# Sheet2.net
KiCad netlist of a schematic drawn in Altium Designer
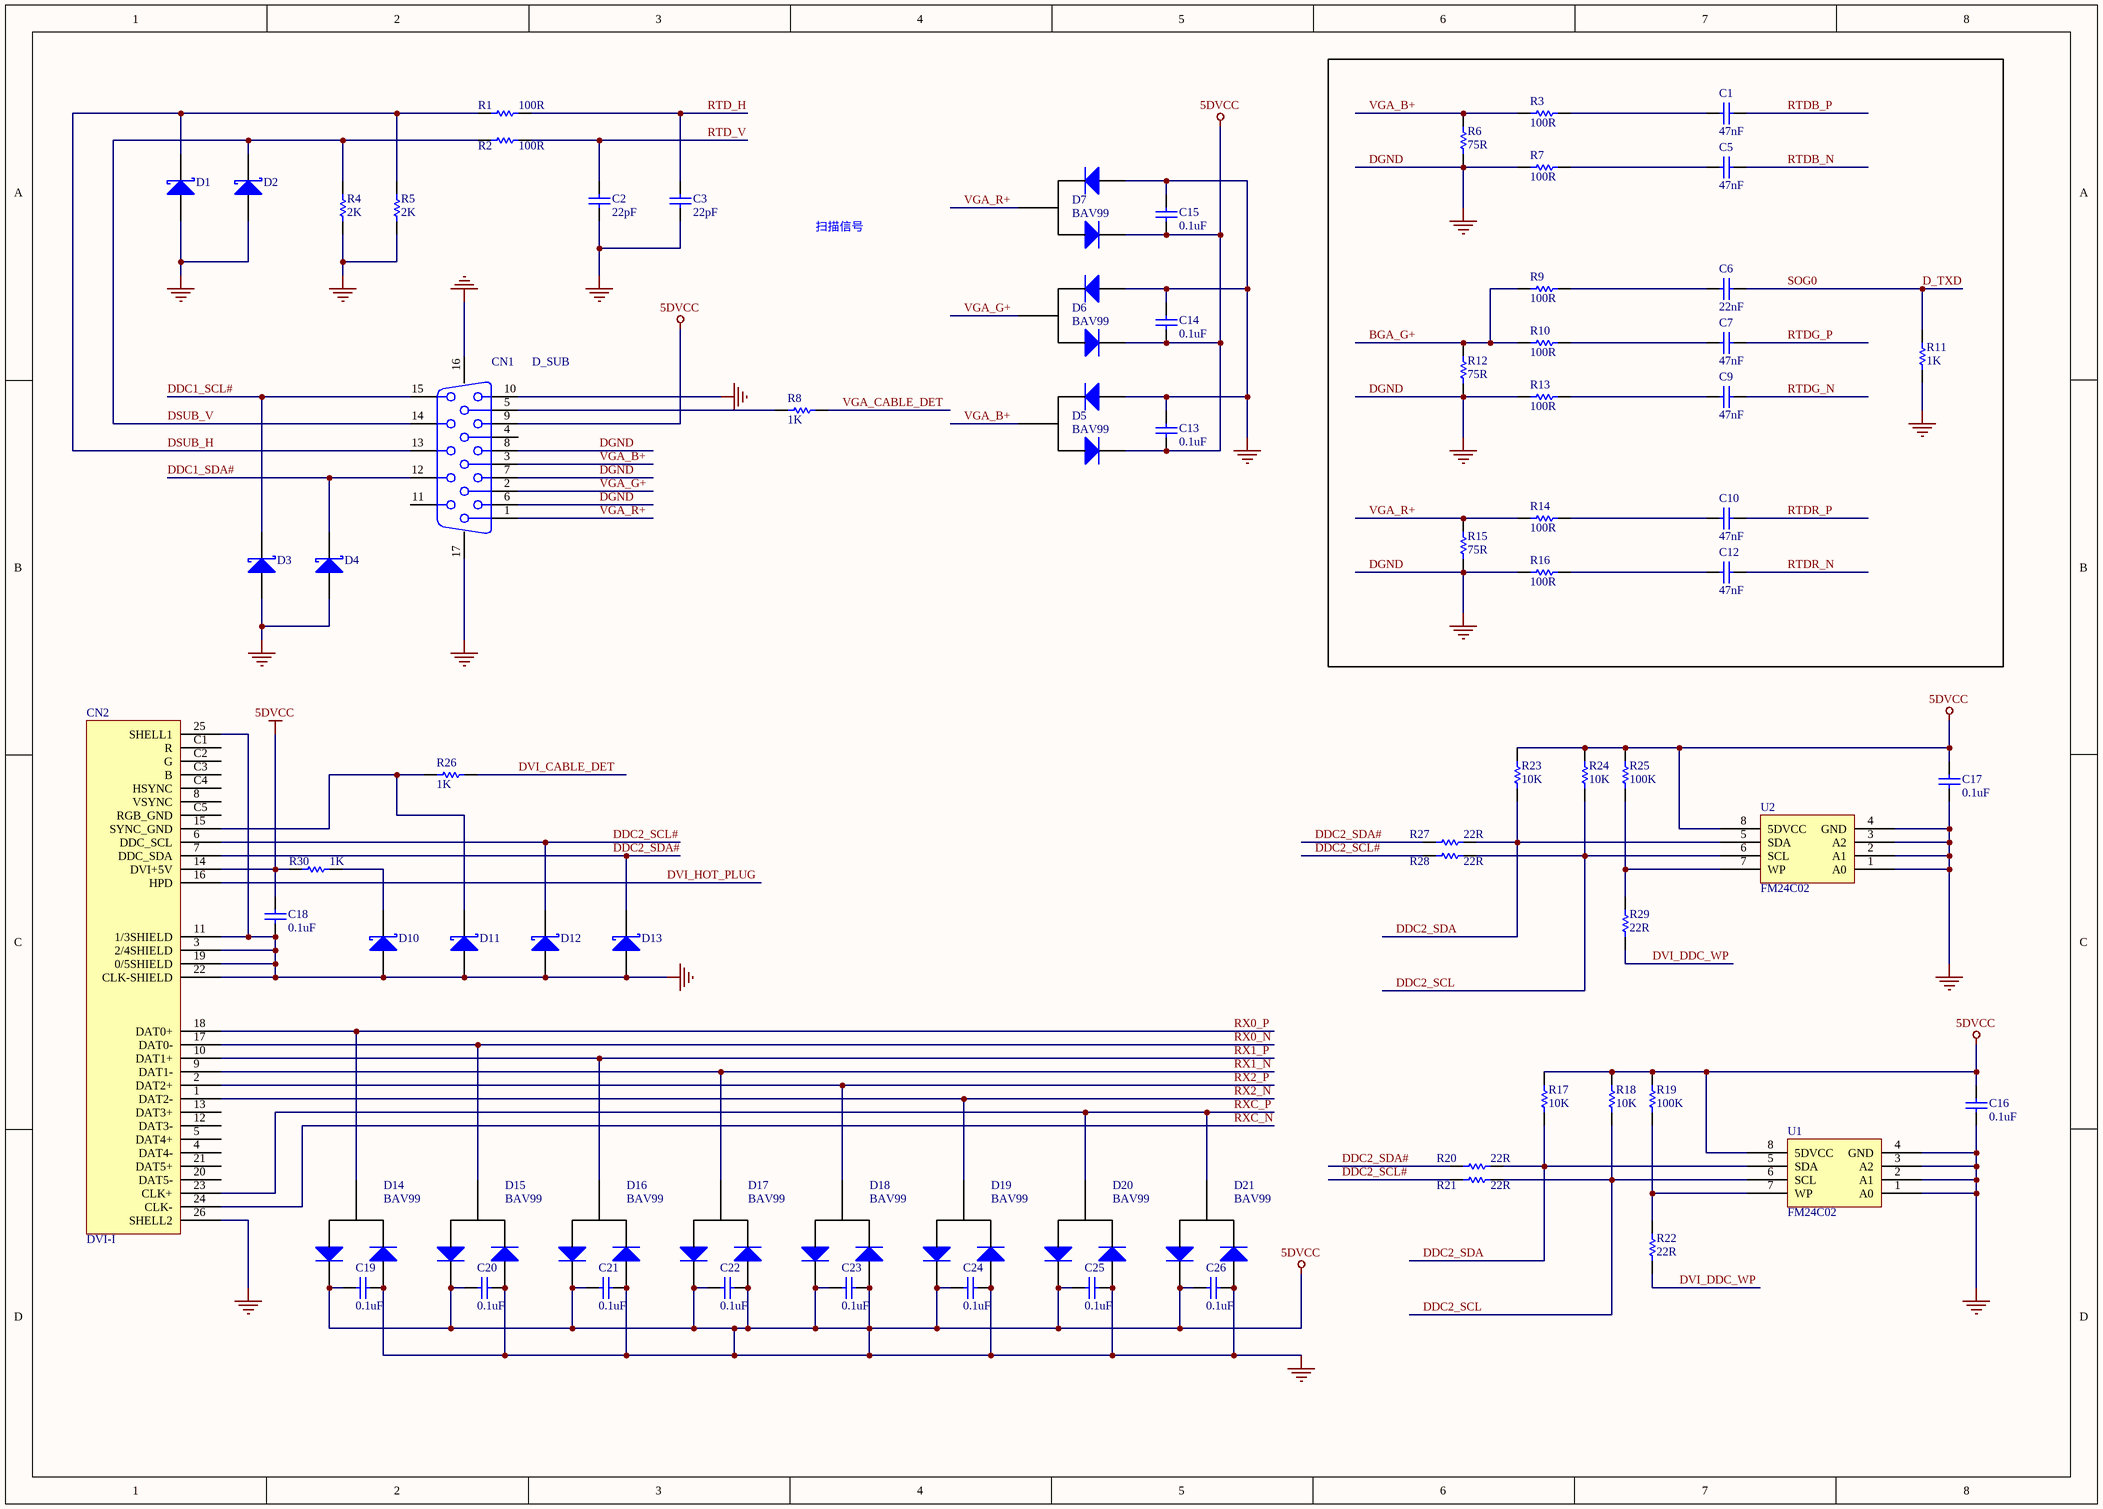
[diagram p0: Sheet2.SchDoc]

(export (version "E")
  (design (tool "Eeschema 10.0.6"))
  (components
    (comp (ref "C1")
      (value "47nF")
      (footprint "C-0402")
      (description "Capacitor")
      (fields (field (name "Comment") "Cap") (field (name "PUBLISHER") "Altium Limited"))
      (libsource (lib "Miscellaneous Devices") (part "Cap"))
    )
    (comp (ref "C2")
      (value "22pF")
      (footprint "C-0402")
      (description "Capacitor")
      (fields (field (name "Comment") "Cap") (field (name "PUBLISHER") "Altium Limited"))
      (libsource (lib "Miscellaneous Devices") (part "Cap"))
    )
    (comp (ref "C3")
      (value "22pF")
      (footprint "C-0402")
      (description "Capacitor")
      (fields (field (name "Comment") "Cap") (field (name "PUBLISHER") "Altium Limited"))
      (libsource (lib "Miscellaneous Devices") (part "Cap"))
    )
    (comp (ref "C5")
      (value "47nF")
      (footprint "C-0402")
      (description "Capacitor")
      (fields (field (name "Comment") "Cap") (field (name "PUBLISHER") "Altium Limited"))
      (libsource (lib "Miscellaneous Devices") (part "Cap"))
    )
    (comp (ref "C6")
      (value "22nF")
      (footprint "C-0402")
      (description "Capacitor")
      (fields (field (name "Comment") "Cap") (field (name "PUBLISHER") "Altium Limited"))
      (libsource (lib "Miscellaneous Devices") (part "Cap"))
    )
    (comp (ref "C7")
      (value "47nF")
      (footprint "C-0402")
      (description "Capacitor")
      (fields (field (name "Comment") "Cap") (field (name "PUBLISHER") "Altium Limited"))
      (libsource (lib "Miscellaneous Devices") (part "Cap"))
    )
    (comp (ref "C9")
      (value "47nF")
      (footprint "C-0402")
      (description "Capacitor")
      (fields (field (name "Comment") "Cap") (field (name "PUBLISHER") "Altium Limited"))
      (libsource (lib "Miscellaneous Devices") (part "Cap"))
    )
    (comp (ref "C10")
      (value "47nF")
      (footprint "C-0402")
      (description "Capacitor")
      (fields (field (name "Comment") "Cap") (field (name "PUBLISHER") "Altium Limited"))
      (libsource (lib "Miscellaneous Devices") (part "Cap"))
    )
    (comp (ref "C12")
      (value "47nF")
      (footprint "C-0402")
      (description "Capacitor")
      (fields (field (name "Comment") "Cap") (field (name "PUBLISHER") "Altium Limited"))
      (libsource (lib "Miscellaneous Devices") (part "Cap"))
    )
    (comp (ref "C13")
      (value "0.1uF")
      (footprint "C-0402")
      (description "Capacitor")
      (fields (field (name "Comment") "Cap") (field (name "PUBLISHER") "Altium Limited"))
      (libsource (lib "Miscellaneous Devices") (part "Cap"))
    )
    (comp (ref "C14")
      (value "0.1uF")
      (footprint "C-0402")
      (description "Capacitor")
      (fields (field (name "Comment") "Cap") (field (name "PUBLISHER") "Altium Limited"))
      (libsource (lib "Miscellaneous Devices") (part "Cap"))
    )
    (comp (ref "C15")
      (value "0.1uF")
      (footprint "C-0402")
      (description "Capacitor")
      (fields (field (name "Comment") "Cap") (field (name "PUBLISHER") "Altium Limited"))
      (libsource (lib "Miscellaneous Devices") (part "Cap"))
    )
    (comp (ref "C16")
      (value "0.1uF")
      (footprint "C-0402")
      (description "Capacitor")
      (fields (field (name "Comment") "Cap") (field (name "PUBLISHER") "Altium Limited"))
      (libsource (lib "Miscellaneous Devices") (part "Cap"))
    )
    (comp (ref "C17")
      (value "0.1uF")
      (footprint "C-0402")
      (description "Capacitor")
      (fields (field (name "Comment") "Cap") (field (name "PUBLISHER") "Altium Limited"))
      (libsource (lib "Miscellaneous Devices") (part "Cap"))
    )
    (comp (ref "C18")
      (value "0.1uF")
      (footprint "C-0402")
      (description "Capacitor")
      (fields (field (name "Comment") "Cap") (field (name "PUBLISHER") "Altium Limited"))
      (libsource (lib "Miscellaneous Devices") (part "Cap"))
    )
    (comp (ref "C19")
      (value "0.1uF")
      (footprint "C-0402")
      (description "Capacitor")
      (fields (field (name "Comment") "Cap") (field (name "PUBLISHER") "Altium Limited"))
      (libsource (lib "Miscellaneous Devices") (part "Cap"))
    )
    (comp (ref "C20")
      (value "0.1uF")
      (footprint "C-0402")
      (description "Capacitor")
      (fields (field (name "Comment") "Cap") (field (name "PUBLISHER") "Altium Limited"))
      (libsource (lib "Miscellaneous Devices") (part "Cap"))
    )
    (comp (ref "C21")
      (value "0.1uF")
      (footprint "C-0402")
      (description "Capacitor")
      (fields (field (name "Comment") "Cap") (field (name "PUBLISHER") "Altium Limited"))
      (libsource (lib "Miscellaneous Devices") (part "Cap"))
    )
    (comp (ref "C22")
      (value "0.1uF")
      (footprint "C-0402")
      (description "Capacitor")
      (fields (field (name "Comment") "Cap") (field (name "PUBLISHER") "Altium Limited"))
      (libsource (lib "Miscellaneous Devices") (part "Cap"))
    )
    (comp (ref "C23")
      (value "0.1uF")
      (footprint "C-0402")
      (description "Capacitor")
      (fields (field (name "Comment") "Cap") (field (name "PUBLISHER") "Altium Limited"))
      (libsource (lib "Miscellaneous Devices") (part "Cap"))
    )
    (comp (ref "C24")
      (value "0.1uF")
      (footprint "C-0402")
      (description "Capacitor")
      (fields (field (name "Comment") "Cap") (field (name "PUBLISHER") "Altium Limited"))
      (libsource (lib "Miscellaneous Devices") (part "Cap"))
    )
    (comp (ref "C25")
      (value "0.1uF")
      (footprint "C-0402")
      (description "Capacitor")
      (fields (field (name "Comment") "Cap") (field (name "PUBLISHER") "Altium Limited"))
      (libsource (lib "Miscellaneous Devices") (part "Cap"))
    )
    (comp (ref "C26")
      (value "0.1uF")
      (footprint "C-0402")
      (description "Capacitor")
      (fields (field (name "Comment") "Cap") (field (name "PUBLISHER") "Altium Limited"))
      (libsource (lib "Miscellaneous Devices") (part "Cap"))
    )
    (comp (ref "CN1") (value "D_SUB") (footprint "DSUB-W15") (libsource (lib "Schlib1") (part "D_SUB")))
    (comp (ref "CN2") (value "DVI-I") (footprint "DVI-W24") (libsource (lib "Schlib1") (part "DVI-I")))
    (comp (ref "D1")
      (value "Diode 10TQ035")
      (footprint "D-SOD323S")
      (description "Schottky Rectifier")
      (fields (field (name "PUBLISHER") "Altium Limited"))
      (libsource (lib "Miscellaneous Devices") (part "Diode 10TQ035"))
    )
    (comp (ref "D2")
      (value "Diode 10TQ035")
      (footprint "D-SOD323S")
      (description "Schottky Rectifier")
      (fields (field (name "PUBLISHER") "Altium Limited"))
      (libsource (lib "Miscellaneous Devices") (part "Diode 10TQ035"))
    )
    (comp (ref "D3")
      (value "Diode 10TQ035")
      (footprint "D-SOD323S")
      (description "Schottky Rectifier")
      (fields (field (name "PUBLISHER") "Altium Limited"))
      (libsource (lib "Miscellaneous Devices") (part "Diode 10TQ035"))
    )
    (comp (ref "D4")
      (value "Diode 10TQ035")
      (footprint "D-SOD323S")
      (description "Schottky Rectifier")
      (fields (field (name "PUBLISHER") "Altium Limited"))
      (libsource (lib "Miscellaneous Devices") (part "Diode 10TQ035"))
    )
    (comp (ref "D5") (value "BAV99") (footprint "Q-SOT23") (libsource (lib "Schlib1") (part "DIODE")))
    (comp (ref "D6") (value "BAV99") (footprint "Q-SOT23") (libsource (lib "Schlib1") (part "DIODE")))
    (comp (ref "D7") (value "BAV99") (footprint "Q-SOT23") (libsource (lib "Schlib1") (part "DIODE")))
    (comp (ref "D10")
      (value "Diode 10TQ035")
      (footprint "D-SOD323S")
      (description "Schottky Rectifier")
      (fields (field (name "PUBLISHER") "Altium Limited"))
      (libsource (lib "Miscellaneous Devices") (part "Diode 10TQ035"))
    )
    (comp (ref "D11")
      (value "Diode 10TQ035")
      (footprint "D-SOD323S")
      (description "Schottky Rectifier")
      (fields (field (name "PUBLISHER") "Altium Limited"))
      (libsource (lib "Miscellaneous Devices") (part "Diode 10TQ035"))
    )
    (comp (ref "D12")
      (value "Diode 10TQ035")
      (footprint "D-SOD323S")
      (description "Schottky Rectifier")
      (fields (field (name "PUBLISHER") "Altium Limited"))
      (libsource (lib "Miscellaneous Devices") (part "Diode 10TQ035"))
    )
    (comp (ref "D13")
      (value "Diode 10TQ035")
      (footprint "D-SOD323S")
      (description "Schottky Rectifier")
      (fields (field (name "PUBLISHER") "Altium Limited"))
      (libsource (lib "Miscellaneous Devices") (part "Diode 10TQ035"))
    )
    (comp (ref "D14") (value "BAV99") (footprint "Q-SOT23") (libsource (lib "Schlib1") (part "DIODE")))
    (comp (ref "D15") (value "BAV99") (footprint "Q-SOT23") (libsource (lib "Schlib1") (part "DIODE")))
    (comp (ref "D16") (value "BAV99") (footprint "Q-SOT23") (libsource (lib "Schlib1") (part "DIODE")))
    (comp (ref "D17") (value "BAV99") (footprint "Q-SOT23") (libsource (lib "Schlib1") (part "DIODE")))
    (comp (ref "D18") (value "BAV99") (footprint "Q-SOT23") (libsource (lib "Schlib1") (part "DIODE")))
    (comp (ref "D19") (value "BAV99") (footprint "Q-SOT23") (libsource (lib "Schlib1") (part "DIODE")))
    (comp (ref "D20") (value "BAV99") (footprint "Q-SOT23") (libsource (lib "Schlib1") (part "DIODE")))
    (comp (ref "D21") (value "BAV99") (footprint "Q-SOT23") (libsource (lib "Schlib1") (part "DIODE")))
    (comp (ref "R1")
      (value "100R")
      (footprint "R-0603")
      (description "Resistor")
      (fields (field (name "Comment") "Res1") (field (name "PUBLISHER") "Altium Limited"))
      (libsource (lib "Miscellaneous Devices") (part "Res1"))
    )
    (comp (ref "R2")
      (value "100R")
      (footprint "R-0603")
      (description "Resistor")
      (fields (field (name "Comment") "Res1") (field (name "PUBLISHER") "Altium Limited"))
      (libsource (lib "Miscellaneous Devices") (part "Res1"))
    )
    (comp (ref "R3")
      (value "100R")
      (footprint "R-0603")
      (description "Resistor")
      (fields (field (name "Comment") "Res1") (field (name "PUBLISHER") "Altium Limited"))
      (libsource (lib "Miscellaneous Devices") (part "Res1"))
    )
    (comp (ref "R4")
      (value "2K")
      (footprint "R-0603")
      (description "Resistor")
      (fields (field (name "Comment") "Res1") (field (name "PUBLISHER") "Altium Limited"))
      (libsource (lib "Miscellaneous Devices") (part "Res1"))
    )
    (comp (ref "R5")
      (value "2K")
      (footprint "R-0603")
      (description "Resistor")
      (fields (field (name "Comment") "Res1") (field (name "PUBLISHER") "Altium Limited"))
      (libsource (lib "Miscellaneous Devices") (part "Res1"))
    )
    (comp (ref "R6")
      (value "75R")
      (footprint "R-0603")
      (description "Resistor")
      (fields (field (name "Comment") "Res1") (field (name "PUBLISHER") "Altium Limited"))
      (libsource (lib "Miscellaneous Devices") (part "Res1"))
    )
    (comp (ref "R7")
      (value "100R")
      (footprint "R-0603")
      (description "Resistor")
      (fields (field (name "Comment") "Res1") (field (name "PUBLISHER") "Altium Limited"))
      (libsource (lib "Miscellaneous Devices") (part "Res1"))
    )
    (comp (ref "R8")
      (value "1K")
      (footprint "R-0603")
      (description "Resistor")
      (fields (field (name "Comment") "Res1") (field (name "PUBLISHER") "Altium Limited"))
      (libsource (lib "Miscellaneous Devices") (part "Res1"))
    )
    (comp (ref "R9")
      (value "100R")
      (footprint "R-0603")
      (description "Resistor")
      (fields (field (name "Comment") "Res1") (field (name "PUBLISHER") "Altium Limited"))
      (libsource (lib "Miscellaneous Devices") (part "Res1"))
    )
    (comp (ref "R10")
      (value "100R")
      (footprint "R-0603")
      (description "Resistor")
      (fields (field (name "Comment") "Res1") (field (name "PUBLISHER") "Altium Limited"))
      (libsource (lib "Miscellaneous Devices") (part "Res1"))
    )
    (comp (ref "R11")
      (value "1K")
      (footprint "R-0603")
      (description "Resistor")
      (fields (field (name "Comment") "Res1") (field (name "PUBLISHER") "Altium Limited"))
      (libsource (lib "Miscellaneous Devices") (part "Res1"))
    )
    (comp (ref "R12")
      (value "75R")
      (footprint "R-0603")
      (description "Resistor")
      (fields (field (name "Comment") "Res1") (field (name "PUBLISHER") "Altium Limited"))
      (libsource (lib "Miscellaneous Devices") (part "Res1"))
    )
    (comp (ref "R13")
      (value "100R")
      (footprint "R-0603")
      (description "Resistor")
      (fields (field (name "Comment") "Res1") (field (name "PUBLISHER") "Altium Limited"))
      (libsource (lib "Miscellaneous Devices") (part "Res1"))
    )
    (comp (ref "R14")
      (value "100R")
      (footprint "R-0603")
      (description "Resistor")
      (fields (field (name "Comment") "Res1") (field (name "PUBLISHER") "Altium Limited"))
      (libsource (lib "Miscellaneous Devices") (part "Res1"))
    )
    (comp (ref "R15")
      (value "75R")
      (footprint "R-0603")
      (description "Resistor")
      (fields (field (name "Comment") "Res1") (field (name "PUBLISHER") "Altium Limited"))
      (libsource (lib "Miscellaneous Devices") (part "Res1"))
    )
    (comp (ref "R16")
      (value "100R")
      (footprint "R-0603")
      (description "Resistor")
      (fields (field (name "Comment") "Res1") (field (name "PUBLISHER") "Altium Limited"))
      (libsource (lib "Miscellaneous Devices") (part "Res1"))
    )
    (comp (ref "R17")
      (value "10K")
      (footprint "R-0603")
      (description "Resistor")
      (fields (field (name "Comment") "Res1") (field (name "PUBLISHER") "Altium Limited"))
      (libsource (lib "Miscellaneous Devices") (part "Res1"))
    )
    (comp (ref "R18")
      (value "10K")
      (footprint "R-0603")
      (description "Resistor")
      (fields (field (name "Comment") "Res1") (field (name "PUBLISHER") "Altium Limited"))
      (libsource (lib "Miscellaneous Devices") (part "Res1"))
    )
    (comp (ref "R19")
      (value "100K")
      (footprint "R-0603")
      (description "Resistor")
      (fields (field (name "Comment") "Res1") (field (name "PUBLISHER") "Altium Limited"))
      (libsource (lib "Miscellaneous Devices") (part "Res1"))
    )
    (comp (ref "R20")
      (value "22R")
      (footprint "R-0603")
      (description "Resistor")
      (fields (field (name "Comment") "Res1") (field (name "PUBLISHER") "Altium Limited"))
      (libsource (lib "Miscellaneous Devices") (part "Res1"))
    )
    (comp (ref "R21")
      (value "22R")
      (footprint "R-0603")
      (description "Resistor")
      (fields (field (name "Comment") "Res1") (field (name "PUBLISHER") "Altium Limited"))
      (libsource (lib "Miscellaneous Devices") (part "Res1"))
    )
    (comp (ref "R22")
      (value "22R")
      (footprint "R-0603")
      (description "Resistor")
      (fields (field (name "Comment") "Res1") (field (name "PUBLISHER") "Altium Limited"))
      (libsource (lib "Miscellaneous Devices") (part "Res1"))
    )
    (comp (ref "R23")
      (value "10K")
      (footprint "R-0603")
      (description "Resistor")
      (fields (field (name "Comment") "Res1") (field (name "PUBLISHER") "Altium Limited"))
      (libsource (lib "Miscellaneous Devices") (part "Res1"))
    )
    (comp (ref "R24")
      (value "10K")
      (footprint "R-0603")
      (description "Resistor")
      (fields (field (name "Comment") "Res1") (field (name "PUBLISHER") "Altium Limited"))
      (libsource (lib "Miscellaneous Devices") (part "Res1"))
    )
    (comp (ref "R25")
      (value "100K")
      (footprint "R-0603")
      (description "Resistor")
      (fields (field (name "Comment") "Res1") (field (name "PUBLISHER") "Altium Limited"))
      (libsource (lib "Miscellaneous Devices") (part "Res1"))
    )
    (comp (ref "R26")
      (value "1K")
      (footprint "R-0603")
      (description "Resistor")
      (fields (field (name "Comment") "Res1") (field (name "PUBLISHER") "Altium Limited"))
      (libsource (lib "Miscellaneous Devices") (part "Res1"))
    )
    (comp (ref "R27")
      (value "22R")
      (footprint "R-0603")
      (description "Resistor")
      (fields (field (name "Comment") "Res1") (field (name "PUBLISHER") "Altium Limited"))
      (libsource (lib "Miscellaneous Devices") (part "Res1"))
    )
    (comp (ref "R28")
      (value "22R")
      (footprint "R-0603")
      (description "Resistor")
      (fields (field (name "Comment") "Res1") (field (name "PUBLISHER") "Altium Limited"))
      (libsource (lib "Miscellaneous Devices") (part "Res1"))
    )
    (comp (ref "R29")
      (value "22R")
      (footprint "R-0603")
      (description "Resistor")
      (fields (field (name "Comment") "Res1") (field (name "PUBLISHER") "Altium Limited"))
      (libsource (lib "Miscellaneous Devices") (part "Res1"))
    )
    (comp (ref "R30")
      (value "1K")
      (footprint "R-0603")
      (description "Resistor")
      (fields (field (name "Comment") "Res1") (field (name "PUBLISHER") "Altium Limited"))
      (libsource (lib "Miscellaneous Devices") (part "Res1"))
    )
    (comp (ref "U1") (value "FM24C02") (footprint "U-SOP/1.3") (libsource (lib "Schlib1") (part "FM24C02")))
    (comp (ref "U2") (value "FM24C02") (footprint "U-SOP/1.3") (libsource (lib "Schlib1") (part "FM24C02")))
  )
  (nets
    (net (code "1") (name "/BGA_G+") (class "Default")
      (node (ref "R10") (pin "1") (pinfunction "1_1") (pintype "passive"))
      (node (ref "R12") (pin "2") (pinfunction "2_2") (pintype "passive"))
      (node (ref "R9") (pin "1") (pinfunction "1_1") (pintype "passive"))
    )
    (net (code "2") (name "/DDC1_SCL#") (class "Default")
      (node (ref "CN1") (pin "15") (pinfunction "15_15") (pintype "passive"))
      (node (ref "D3") (pin "1") (pinfunction "K_1") (pintype "passive"))
    )
    (net (code "3") (name "/DDC1_SDA#") (class "Default")
      (node (ref "CN1") (pin "12") (pinfunction "12_12") (pintype "passive"))
      (node (ref "D4") (pin "1") (pinfunction "K_1") (pintype "passive"))
    )
    (net (code "4") (name "/DDC2_SCL") (class "Default")
      (node (ref "R18") (pin "1") (pinfunction "1_1") (pintype "passive"))
      (node (ref "R21") (pin "2") (pinfunction "2_2") (pintype "passive"))
      (node (ref "R24") (pin "1") (pinfunction "1_1") (pintype "passive"))
      (node (ref "R28") (pin "2") (pinfunction "2_2") (pintype "passive"))
      (node (ref "U1") (pin "6") (pinfunction "SCL_6") (pintype "passive"))
      (node (ref "U2") (pin "6") (pinfunction "SCL_6") (pintype "passive"))
    )
    (net (code "5") (name "/DDC2_SCL#") (class "Default")
      (node (ref "CN2") (pin "6") (pinfunction "DDC_SCL_6") (pintype "passive"))
      (node (ref "D12") (pin "1") (pinfunction "K_1") (pintype "passive"))
      (node (ref "R21") (pin "1") (pinfunction "1_1") (pintype "passive"))
      (node (ref "R28") (pin "1") (pinfunction "1_1") (pintype "passive"))
    )
    (net (code "6") (name "/DDC2_SDA") (class "Default")
      (node (ref "R17") (pin "1") (pinfunction "1_1") (pintype "passive"))
      (node (ref "R20") (pin "2") (pinfunction "2_2") (pintype "passive"))
      (node (ref "R23") (pin "1") (pinfunction "1_1") (pintype "passive"))
      (node (ref "R27") (pin "2") (pinfunction "2_2") (pintype "passive"))
      (node (ref "U1") (pin "5") (pinfunction "SDA_5") (pintype "passive"))
      (node (ref "U2") (pin "5") (pinfunction "SDA_5") (pintype "passive"))
    )
    (net (code "7") (name "/DDC2_SDA#") (class "Default")
      (node (ref "CN2") (pin "7") (pinfunction "DDC_SDA_7") (pintype "passive"))
      (node (ref "D13") (pin "1") (pinfunction "K_1") (pintype "passive"))
      (node (ref "R20") (pin "1") (pinfunction "1_1") (pintype "passive"))
      (node (ref "R27") (pin "1") (pinfunction "1_1") (pintype "passive"))
    )
    (net (code "8") (name "/DSUB_H") (class "Default")
      (node (ref "CN1") (pin "13") (pinfunction "13_13") (pintype "passive"))
      (node (ref "D1") (pin "1") (pinfunction "K_1") (pintype "passive"))
      (node (ref "R1") (pin "1") (pinfunction "1_1") (pintype "passive"))
      (node (ref "R5") (pin "2") (pinfunction "2_2") (pintype "passive"))
    )
    (net (code "9") (name "/DSUB_V") (class "Default")
      (node (ref "CN1") (pin "14") (pinfunction "14_14") (pintype "passive"))
      (node (ref "D2") (pin "1") (pinfunction "K_1") (pintype "passive"))
      (node (ref "R2") (pin "1") (pinfunction "1_1") (pintype "passive"))
      (node (ref "R4") (pin "2") (pinfunction "2_2") (pintype "passive"))
    )
    (net (code "10") (name "/DVI_CABLE_DET") (class "Default")
      (node (ref "R26") (pin "2") (pinfunction "2_2") (pintype "passive"))
    )
    (net (code "11") (name "/DVI_DDC_WP") (class "Default")
      (node (ref "R22") (pin "1") (pinfunction "1_1") (pintype "passive"))
      (node (ref "R29") (pin "1") (pinfunction "1_1") (pintype "passive"))
    )
    (net (code "12") (name "/DVI_HOT_PLUG") (class "Default")
      (node (ref "CN2") (pin "16") (pinfunction "HPD_16") (pintype "passive"))
    )
    (net (code "13") (name "/D_TXD") (class "Default")
      (node (ref "C6") (pin "2") (pinfunction "2_2") (pintype "passive"))
      (node (ref "R11") (pin "2") (pinfunction "2_2") (pintype "passive"))
    )
    (net (code "14") (name "/RTDB_N") (class "Default")
      (node (ref "C5") (pin "2") (pinfunction "2_2") (pintype "passive"))
    )
    (net (code "15") (name "/RTDB_P") (class "Default")
      (node (ref "C1") (pin "2") (pinfunction "2_2") (pintype "passive"))
    )
    (net (code "16") (name "/RTDG_N") (class "Default")
      (node (ref "C9") (pin "2") (pinfunction "2_2") (pintype "passive"))
    )
    (net (code "17") (name "/RTDG_P") (class "Default")
      (node (ref "C7") (pin "2") (pinfunction "2_2") (pintype "passive"))
    )
    (net (code "18") (name "/RTDR_N") (class "Default")
      (node (ref "C12") (pin "2") (pinfunction "2_2") (pintype "passive"))
    )
    (net (code "19") (name "/RTDR_P") (class "Default")
      (node (ref "C10") (pin "2") (pinfunction "2_2") (pintype "passive"))
    )
    (net (code "20") (name "/RTD_H") (class "Default")
      (node (ref "C3") (pin "2") (pinfunction "2_2") (pintype "passive"))
      (node (ref "R1") (pin "2") (pinfunction "2_2") (pintype "passive"))
    )
    (net (code "21") (name "/RTD_V") (class "Default")
      (node (ref "C2") (pin "2") (pinfunction "2_2") (pintype "passive"))
      (node (ref "R2") (pin "2") (pinfunction "2_2") (pintype "passive"))
    )
    (net (code "22") (name "/RX0_N") (class "Default")
      (node (ref "CN2") (pin "17") (pinfunction "DAT0-_17") (pintype "passive"))
      (node (ref "D15") (pin "1") (pinfunction "1_1") (pintype "passive"))
    )
    (net (code "23") (name "/RX0_P") (class "Default")
      (node (ref "CN2") (pin "18") (pinfunction "DAT0+_18") (pintype "passive"))
      (node (ref "D14") (pin "1") (pinfunction "1_1") (pintype "passive"))
    )
    (net (code "24") (name "/RX1_N") (class "Default")
      (node (ref "CN2") (pin "9") (pinfunction "DAT1-_9") (pintype "passive"))
      (node (ref "D17") (pin "1") (pinfunction "1_1") (pintype "passive"))
    )
    (net (code "25") (name "/RX1_P") (class "Default")
      (node (ref "CN2") (pin "10") (pinfunction "DAT1+_10") (pintype "passive"))
      (node (ref "D16") (pin "1") (pinfunction "1_1") (pintype "passive"))
    )
    (net (code "26") (name "/RX2_N") (class "Default")
      (node (ref "CN2") (pin "1") (pinfunction "DAT2-_1") (pintype "passive"))
      (node (ref "D19") (pin "1") (pinfunction "1_1") (pintype "passive"))
    )
    (net (code "27") (name "/RX2_P") (class "Default")
      (node (ref "CN2") (pin "2") (pinfunction "DAT2+_2") (pintype "passive"))
      (node (ref "D18") (pin "1") (pinfunction "1_1") (pintype "passive"))
    )
    (net (code "28") (name "/RXC_N") (class "Default")
      (node (ref "CN2") (pin "24") (pinfunction "CLK-_24") (pintype "passive"))
    )
    (net (code "29") (name "/RXC_P") (class "Default")
      (node (ref "CN2") (pin "23") (pinfunction "CLK+_23") (pintype "passive"))
      (node (ref "D20") (pin "1") (pinfunction "1_1") (pintype "passive"))
      (node (ref "D21") (pin "1") (pinfunction "1_1") (pintype "passive"))
    )
    (net (code "30") (name "/VGA_B+") (class "Default")
      (node (ref "CN1") (pin "3") (pinfunction "3_3") (pintype "passive"))
      (node (ref "D5") (pin "1") (pinfunction "1_1") (pintype "passive"))
      (node (ref "R3") (pin "1") (pinfunction "1_1") (pintype "passive"))
      (node (ref "R6") (pin "2") (pinfunction "2_2") (pintype "passive"))
    )
    (net (code "31") (name "/VGA_CABLE_DET") (class "Default")
      (node (ref "R8") (pin "2") (pinfunction "2_2") (pintype "passive"))
    )
    (net (code "32") (name "/VGA_G+") (class "Default")
      (node (ref "CN1") (pin "2") (pinfunction "2_2") (pintype "passive"))
      (node (ref "D6") (pin "1") (pinfunction "1_1") (pintype "passive"))
    )
    (net (code "33") (name "/VGA_R+") (class "Default")
      (node (ref "CN1") (pin "1") (pinfunction "1_1") (pintype "passive"))
      (node (ref "D7") (pin "1") (pinfunction "1_1") (pintype "passive"))
      (node (ref "R14") (pin "1") (pinfunction "1_1") (pintype "passive"))
      (node (ref "R15") (pin "2") (pinfunction "2_2") (pintype "passive"))
    )
    (net (code "34") (name "5DVCC") (class "Default")
      (node (ref "C13") (pin "1") (pinfunction "1_1") (pintype "passive"))
      (node (ref "C13") (pin "2") (pinfunction "2_2") (pintype "passive"))
      (node (ref "C14") (pin "1") (pinfunction "1_1") (pintype "passive"))
      (node (ref "C14") (pin "2") (pinfunction "2_2") (pintype "passive"))
      (node (ref "C15") (pin "1") (pinfunction "1_1") (pintype "passive"))
      (node (ref "C15") (pin "2") (pinfunction "2_2") (pintype "passive"))
      (node (ref "C16") (pin "1") (pinfunction "1_1") (pintype "passive"))
      (node (ref "C16") (pin "2") (pinfunction "2_2") (pintype "passive"))
      (node (ref "C17") (pin "1") (pinfunction "1_1") (pintype "passive"))
      (node (ref "C17") (pin "2") (pinfunction "2_2") (pintype "passive"))
      (node (ref "C18") (pin "1") (pinfunction "1_1") (pintype "passive"))
      (node (ref "C18") (pin "2") (pinfunction "2_2") (pintype "passive"))
      (node (ref "C19") (pin "1") (pinfunction "1_1") (pintype "passive"))
      (node (ref "C19") (pin "2") (pinfunction "2_2") (pintype "passive"))
      (node (ref "C2") (pin "1") (pinfunction "1_1") (pintype "passive"))
      (node (ref "C20") (pin "1") (pinfunction "1_1") (pintype "passive"))
      (node (ref "C20") (pin "2") (pinfunction "2_2") (pintype "passive"))
      (node (ref "C21") (pin "1") (pinfunction "1_1") (pintype "passive"))
      (node (ref "C21") (pin "2") (pinfunction "2_2") (pintype "passive"))
      (node (ref "C22") (pin "1") (pinfunction "1_1") (pintype "passive"))
      (node (ref "C22") (pin "2") (pinfunction "2_2") (pintype "passive"))
      (node (ref "C23") (pin "1") (pinfunction "1_1") (pintype "passive"))
      (node (ref "C23") (pin "2") (pinfunction "2_2") (pintype "passive"))
      (node (ref "C24") (pin "1") (pinfunction "1_1") (pintype "passive"))
      (node (ref "C24") (pin "2") (pinfunction "2_2") (pintype "passive"))
      (node (ref "C25") (pin "1") (pinfunction "1_1") (pintype "passive"))
      (node (ref "C25") (pin "2") (pinfunction "2_2") (pintype "passive"))
      (node (ref "C26") (pin "1") (pinfunction "1_1") (pintype "passive"))
      (node (ref "C26") (pin "2") (pinfunction "2_2") (pintype "passive"))
      (node (ref "C3") (pin "1") (pinfunction "1_1") (pintype "passive"))
      (node (ref "CN1") (pin "10") (pinfunction "10_10") (pintype "passive"))
      (node (ref "CN1") (pin "16") (pinfunction "MH1_16") (pintype "passive"))
      (node (ref "CN1") (pin "17") (pinfunction "MH2_17") (pintype "passive"))
      (node (ref "CN1") (pin "6") (pinfunction "6_6") (pintype "passive"))
      (node (ref "CN1") (pin "7") (pinfunction "7_7") (pintype "passive"))
      (node (ref "CN1") (pin "8") (pinfunction "8_8") (pintype "passive"))
      (node (ref "CN1") (pin "9") (pinfunction "9_9") (pintype "passive"))
      (node (ref "CN2") (pin "11") (pinfunction "1/3SHIELD_11") (pintype "passive"))
      (node (ref "CN2") (pin "14") (pinfunction "DVI+5V_14") (pintype "passive"))
      (node (ref "CN2") (pin "19") (pinfunction "0/5SHIELD_19") (pintype "passive"))
      (node (ref "CN2") (pin "22") (pinfunction "CLK-SHIELD_22") (pintype "passive"))
      (node (ref "CN2") (pin "25") (pinfunction "SHELL1_25") (pintype "passive"))
      (node (ref "CN2") (pin "26") (pinfunction "SHELL2_26") (pintype "passive"))
      (node (ref "CN2") (pin "3") (pinfunction "2/4SHIELD_3") (pintype "passive"))
      (node (ref "D1") (pin "3") (pinfunction "A_3") (pintype "passive"))
      (node (ref "D10") (pin "3") (pinfunction "A_3") (pintype "passive"))
      (node (ref "D11") (pin "3") (pinfunction "A_3") (pintype "passive"))
      (node (ref "D12") (pin "3") (pinfunction "A_3") (pintype "passive"))
      (node (ref "D13") (pin "3") (pinfunction "A_3") (pintype "passive"))
      (node (ref "D14") (pin "2") (pinfunction "2_2") (pintype "passive"))
      (node (ref "D14") (pin "3") (pinfunction "3_3") (pintype "passive"))
      (node (ref "D15") (pin "2") (pinfunction "2_2") (pintype "passive"))
      (node (ref "D15") (pin "3") (pinfunction "3_3") (pintype "passive"))
      (node (ref "D16") (pin "2") (pinfunction "2_2") (pintype "passive"))
      (node (ref "D16") (pin "3") (pinfunction "3_3") (pintype "passive"))
      (node (ref "D17") (pin "2") (pinfunction "2_2") (pintype "passive"))
      (node (ref "D17") (pin "3") (pinfunction "3_3") (pintype "passive"))
      (node (ref "D18") (pin "2") (pinfunction "2_2") (pintype "passive"))
      (node (ref "D18") (pin "3") (pinfunction "3_3") (pintype "passive"))
      (node (ref "D19") (pin "2") (pinfunction "2_2") (pintype "passive"))
      (node (ref "D19") (pin "3") (pinfunction "3_3") (pintype "passive"))
      (node (ref "D2") (pin "3") (pinfunction "A_3") (pintype "passive"))
      (node (ref "D20") (pin "2") (pinfunction "2_2") (pintype "passive"))
      (node (ref "D20") (pin "3") (pinfunction "3_3") (pintype "passive"))
      (node (ref "D21") (pin "2") (pinfunction "2_2") (pintype "passive"))
      (node (ref "D21") (pin "3") (pinfunction "3_3") (pintype "passive"))
      (node (ref "D3") (pin "3") (pinfunction "A_3") (pintype "passive"))
      (node (ref "D4") (pin "3") (pinfunction "A_3") (pintype "passive"))
      (node (ref "D5") (pin "2") (pinfunction "2_2") (pintype "passive"))
      (node (ref "D5") (pin "3") (pinfunction "3_3") (pintype "passive"))
      (node (ref "D6") (pin "2") (pinfunction "2_2") (pintype "passive"))
      (node (ref "D6") (pin "3") (pinfunction "3_3") (pintype "passive"))
      (node (ref "D7") (pin "2") (pinfunction "2_2") (pintype "passive"))
      (node (ref "D7") (pin "3") (pinfunction "3_3") (pintype "passive"))
      (node (ref "R11") (pin "1") (pinfunction "1_1") (pintype "passive"))
      (node (ref "R12") (pin "1") (pinfunction "1_1") (pintype "passive"))
      (node (ref "R13") (pin "1") (pinfunction "1_1") (pintype "passive"))
      (node (ref "R15") (pin "1") (pinfunction "1_1") (pintype "passive"))
      (node (ref "R16") (pin "1") (pinfunction "1_1") (pintype "passive"))
      (node (ref "R17") (pin "2") (pinfunction "2_2") (pintype "passive"))
      (node (ref "R18") (pin "2") (pinfunction "2_2") (pintype "passive"))
      (node (ref "R19") (pin "2") (pinfunction "2_2") (pintype "passive"))
      (node (ref "R23") (pin "2") (pinfunction "2_2") (pintype "passive"))
      (node (ref "R24") (pin "2") (pinfunction "2_2") (pintype "passive"))
      (node (ref "R25") (pin "2") (pinfunction "2_2") (pintype "passive"))
      (node (ref "R30") (pin "1") (pinfunction "1_1") (pintype "passive"))
      (node (ref "R4") (pin "1") (pinfunction "1_1") (pintype "passive"))
      (node (ref "R5") (pin "1") (pinfunction "1_1") (pintype "passive"))
      (node (ref "R6") (pin "1") (pinfunction "1_1") (pintype "passive"))
      (node (ref "R7") (pin "1") (pinfunction "1_1") (pintype "passive"))
      (node (ref "U1") (pin "1") (pinfunction "A0_1") (pintype "passive"))
      (node (ref "U1") (pin "2") (pinfunction "A1_2") (pintype "passive"))
      (node (ref "U1") (pin "3") (pinfunction "A2_3") (pintype "passive"))
      (node (ref "U1") (pin "4") (pinfunction "GND_4") (pintype "passive"))
      (node (ref "U1") (pin "8") (pinfunction "5DVCC_8") (pintype "passive"))
      (node (ref "U2") (pin "1") (pinfunction "A0_1") (pintype "passive"))
      (node (ref "U2") (pin "2") (pinfunction "A1_2") (pintype "passive"))
      (node (ref "U2") (pin "3") (pinfunction "A2_3") (pintype "passive"))
      (node (ref "U2") (pin "4") (pinfunction "GND_4") (pintype "passive"))
      (node (ref "U2") (pin "8") (pinfunction "5DVCC_8") (pintype "passive"))
    )
    (net (code "35") (name "Net-(C1-Pad1)") (class "Default")
      (node (ref "C1") (pin "1") (pinfunction "1_1") (pintype "passive"))
      (node (ref "R3") (pin "2") (pinfunction "2_2") (pintype "passive"))
    )
    (net (code "36") (name "Net-(C5-Pad1)") (class "Default")
      (node (ref "C5") (pin "1") (pinfunction "1_1") (pintype "passive"))
      (node (ref "R7") (pin "2") (pinfunction "2_2") (pintype "passive"))
    )
    (net (code "37") (name "Net-(C6-Pad1)") (class "Default")
      (node (ref "C6") (pin "1") (pinfunction "1_1") (pintype "passive"))
      (node (ref "R9") (pin "2") (pinfunction "2_2") (pintype "passive"))
    )
    (net (code "38") (name "Net-(C7-Pad1)") (class "Default")
      (node (ref "C7") (pin "1") (pinfunction "1_1") (pintype "passive"))
      (node (ref "R10") (pin "2") (pinfunction "2_2") (pintype "passive"))
    )
    (net (code "39") (name "Net-(C9-Pad1)") (class "Default")
      (node (ref "C9") (pin "1") (pinfunction "1_1") (pintype "passive"))
      (node (ref "R13") (pin "2") (pinfunction "2_2") (pintype "passive"))
    )
    (net (code "40") (name "Net-(C10-Pad1)") (class "Default")
      (node (ref "C10") (pin "1") (pinfunction "1_1") (pintype "passive"))
      (node (ref "R14") (pin "2") (pinfunction "2_2") (pintype "passive"))
    )
    (net (code "41") (name "Net-(C12-Pad1)") (class "Default")
      (node (ref "C12") (pin "1") (pinfunction "1_1") (pintype "passive"))
      (node (ref "R16") (pin "2") (pinfunction "2_2") (pintype "passive"))
    )
    (net (code "42") (name "Net-(CN1-Pad5)") (class "Default")
      (node (ref "CN1") (pin "5") (pinfunction "5_5") (pintype "passive"))
      (node (ref "R8") (pin "1") (pinfunction "1_1") (pintype "passive"))
    )
    (net (code "43") (name "Net-(CN2-SYNC_GND)") (class "Default")
      (node (ref "CN2") (pin "15") (pinfunction "SYNC_GND_15") (pintype "passive"))
      (node (ref "D11") (pin "1") (pinfunction "K_1") (pintype "passive"))
      (node (ref "R26") (pin "1") (pinfunction "1_1") (pintype "passive"))
    )
    (net (code "44") (name "Net-(D10-K)") (class "Default")
      (node (ref "D10") (pin "1") (pinfunction "K_1") (pintype "passive"))
      (node (ref "R30") (pin "2") (pinfunction "2_2") (pintype "passive"))
    )
    (net (code "45") (name "Net-(U1-WP)") (class "Default")
      (node (ref "R19") (pin "1") (pinfunction "1_1") (pintype "passive"))
      (node (ref "R22") (pin "2") (pinfunction "2_2") (pintype "passive"))
      (node (ref "U1") (pin "7") (pinfunction "WP_7") (pintype "passive"))
    )
    (net (code "46") (name "Net-(U2-WP)") (class "Default")
      (node (ref "R25") (pin "1") (pinfunction "1_1") (pintype "passive"))
      (node (ref "R29") (pin "2") (pinfunction "2_2") (pintype "passive"))
      (node (ref "U2") (pin "7") (pinfunction "WP_7") (pintype "passive"))
    )
    (net (code "47") (name "unconnected-(CN1-Pad4)") (class "Default")
      (node (ref "CN1") (pin "4") (pinfunction "4_4") (pintype "passive"))
    )
    (net (code "48") (name "unconnected-(CN1-Pad11)") (class "Default")
      (node (ref "CN1") (pin "11") (pinfunction "11_11") (pintype "passive"))
    )
    (net (code "49") (name "unconnected-(CN2-B-PadC3)") (class "Default")
      (node (ref "CN2") (pin "C3") (pinfunction "B_C3") (pintype "passive"))
    )
    (net (code "50") (name "unconnected-(CN2-DAT3+-Pad13)") (class "Default")
      (node (ref "CN2") (pin "13") (pinfunction "DAT3+_13") (pintype "passive"))
    )
    (net (code "51") (name "unconnected-(CN2-DAT3--Pad12)") (class "Default")
      (node (ref "CN2") (pin "12") (pinfunction "DAT3-_12") (pintype "passive"))
    )
    (net (code "52") (name "unconnected-(CN2-DAT4+-Pad5)") (class "Default")
      (node (ref "CN2") (pin "5") (pinfunction "DAT4+_5") (pintype "passive"))
    )
    (net (code "53") (name "unconnected-(CN2-DAT4--Pad4)") (class "Default")
      (node (ref "CN2") (pin "4") (pinfunction "DAT4-_4") (pintype "passive"))
    )
    (net (code "54") (name "unconnected-(CN2-DAT5+-Pad21)") (class "Default")
      (node (ref "CN2") (pin "21") (pinfunction "DAT5+_21") (pintype "passive"))
    )
    (net (code "55") (name "unconnected-(CN2-DAT5--Pad20)") (class "Default")
      (node (ref "CN2") (pin "20") (pinfunction "DAT5-_20") (pintype "passive"))
    )
    (net (code "56") (name "unconnected-(CN2-G-PadC2)") (class "Default")
      (node (ref "CN2") (pin "C2") (pinfunction "G_C2") (pintype "passive"))
    )
    (net (code "57") (name "unconnected-(CN2-HSYNC-PadC4)") (class "Default")
      (node (ref "CN2") (pin "C4") (pinfunction "HSYNC_C4") (pintype "passive"))
    )
    (net (code "58") (name "unconnected-(CN2-R-PadC1)") (class "Default")
      (node (ref "CN2") (pin "C1") (pinfunction "R_C1") (pintype "passive"))
    )
    (net (code "59") (name "unconnected-(CN2-RGB_GND-PadC5)") (class "Default")
      (node (ref "CN2") (pin "C5") (pinfunction "RGB_GND_C5") (pintype "passive"))
    )
    (net (code "60") (name "unconnected-(CN2-VSYNC-Pad8)") (class "Default")
      (node (ref "CN2") (pin "8") (pinfunction "VSYNC_8") (pintype "passive"))
    )
  )
)
